# MCU_board_3.net
KiCad netlist of a schematic drawn in Altium Designer
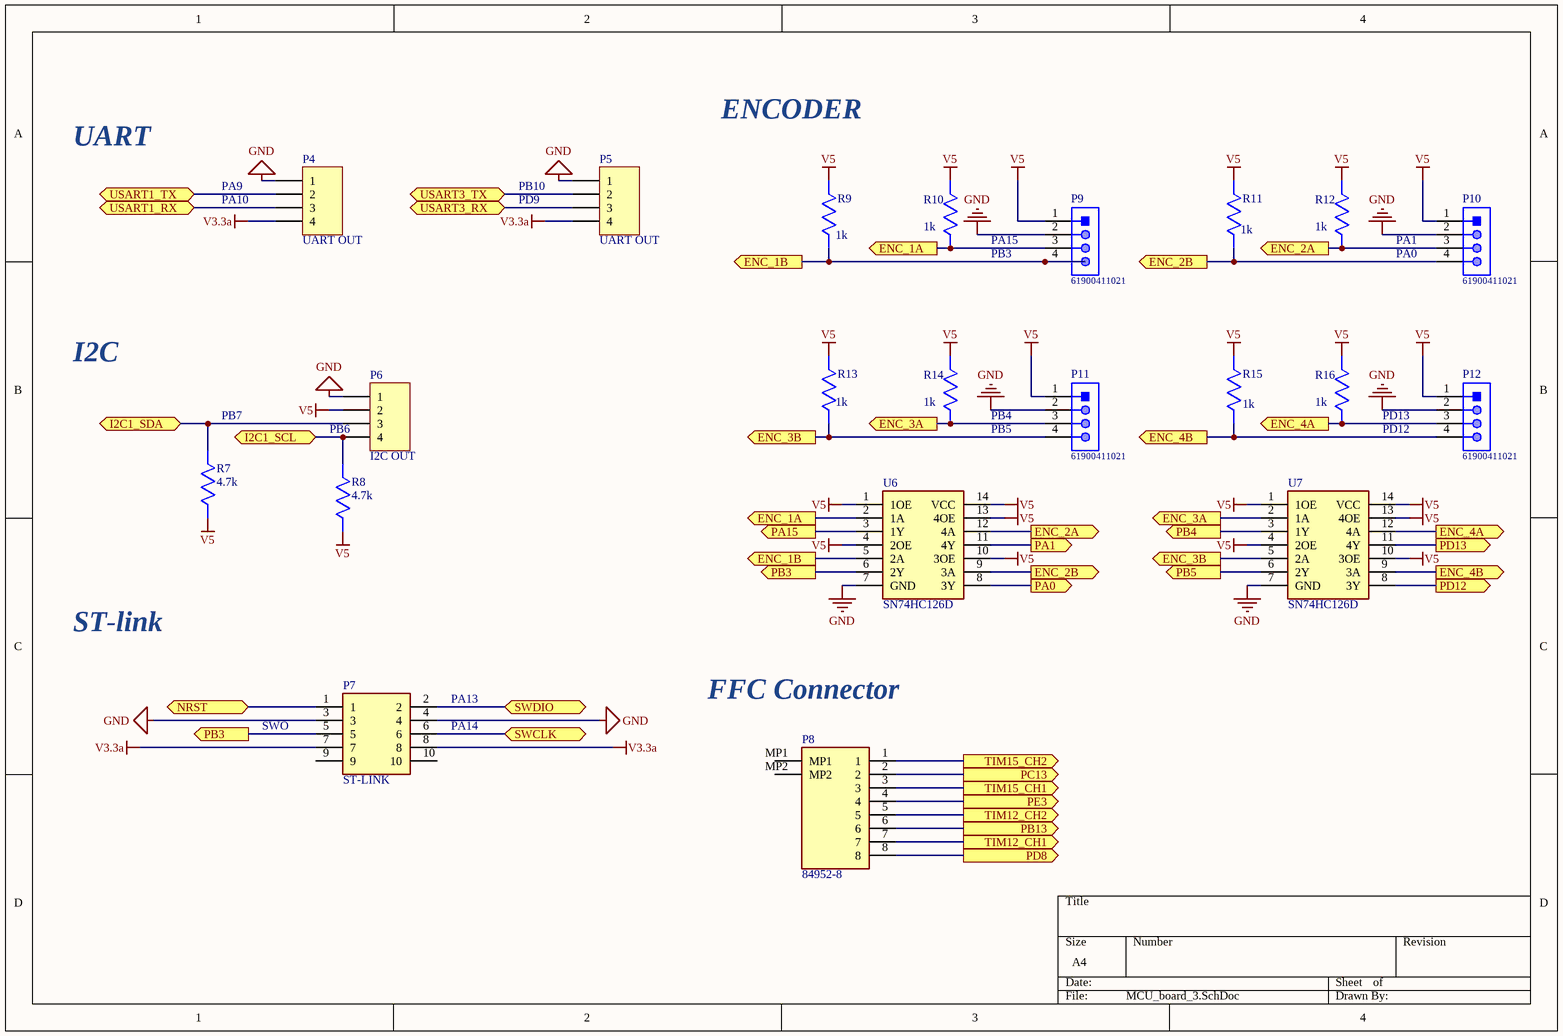
[diagram p0: MCU_board_3.SchDoc]

(export (version "E")
  (design (tool "Eeschema 10.0.6"))
  (components
    (comp (ref "P4")
      (value "UART OUT")
      (footprint "HDR1X4")
      (description "Header, 4-Pin")
      (fields (field (name "PUBLISHER") "Altium Limited"))
      (libsource (lib "Miscellaneous Connectors") (part "Header 4"))
    )
    (comp (ref "P5")
      (value "UART OUT")
      (footprint "HDR1X4")
      (description "Header, 4-Pin")
      (fields (field (name "PUBLISHER") "Altium Limited"))
      (libsource (lib "Miscellaneous Connectors") (part "Header 4"))
    )
    (comp (ref "P6")
      (value "I2C OUT")
      (footprint "HDR1X4")
      (description "Header, 4-Pin")
      (fields (field (name "PUBLISHER") "Altium Limited"))
      (libsource (lib "Miscellaneous Connectors") (part "Header 4"))
    )
    (comp (ref "P7")
      (value "ST-LINK")
      (footprint "SamacSys:SHDR10W66P254_2X5_2035X880X920P")
      (description "Connector")
      (fields (field (name "MANUFACTURER_PART_NUMBER") "1-1634688-0"))
      (libsource (lib "*") (part "1-1634688-0"))
    )
    (comp (ref "P8")
      (value "84952-8")
      (footprint "SamacSys:849528")
      (description "Connector")
      (fields (field (name "MOUSER PART NUMBER") "571-84952-8"))
      (libsource (lib "*") (part "84952-8"))
    )
    (comp (ref "P9")
      (value "61900411021")
      (footprint "61900411021")
      (description "Male Bottom Locking Header WR-WTB, THT, Right Angled, pitch 2.54 mm, 1 x 4 position")
      (fields (field (name "MANUFACTURER") "Wurth Elektronik") (field (name "PUBLISHER") "WurthElektronik"))
      (libsource (lib "Altium Content Vault") (part "WE-CN-1P-M-R4"))
    )
    (comp (ref "P10")
      (value "61900411021")
      (footprint "61900411021")
      (description "Male Bottom Locking Header WR-WTB, THT, Right Angled, pitch 2.54 mm, 1 x 4 position")
      (fields (field (name "MANUFACTURER") "Wurth Elektronik") (field (name "PUBLISHER") "WurthElektronik"))
      (libsource (lib "Altium Content Vault") (part "WE-CN-1P-M-R4"))
    )
    (comp (ref "P11")
      (value "61900411021")
      (footprint "61900411021")
      (description "Male Bottom Locking Header WR-WTB, THT, Right Angled, pitch 2.54 mm, 1 x 4 position")
      (fields (field (name "MANUFACTURER") "Wurth Elektronik") (field (name "PUBLISHER") "WurthElektronik"))
      (libsource (lib "Altium Content Vault") (part "WE-CN-1P-M-R4"))
    )
    (comp (ref "P12")
      (value "61900411021")
      (footprint "61900411021")
      (description "Male Bottom Locking Header WR-WTB, THT, Right Angled, pitch 2.54 mm, 1 x 4 position")
      (fields (field (name "MANUFACTURER") "Wurth Elektronik") (field (name "PUBLISHER") "WurthElektronik"))
      (libsource (lib "Altium Content Vault") (part "WE-CN-1P-M-R4"))
    )
    (comp (ref "R7")
      (value "4.7k")
      (footprint "SamacSys:RESC1608X55N")
      (description "Resistor")
      (fields (field (name "MANUFACTURER_PART_NUMBER") "CMP0603-FX-1003ELF"))
      (libsource (lib "SamacSys") (part "CMP0603-FX-1003ELF"))
    )
    (comp (ref "R8")
      (value "4.7k")
      (footprint "SamacSys:RESC1608X55N")
      (description "Resistor")
      (fields (field (name "MANUFACTURER_PART_NUMBER") "CMP0603-FX-1003ELF"))
      (libsource (lib "SamacSys") (part "CMP0603-FX-1003ELF"))
    )
    (comp (ref "R9")
      (value "1k")
      (footprint "SamacSys:RESC1608X55N")
      (description "Resistor")
      (fields (field (name "MANUFACTURER_PART_NUMBER") "CMP0603-FX-1003ELF"))
      (libsource (lib "SamacSys") (part "CMP0603-FX-1003ELF"))
    )
    (comp (ref "R10")
      (value "1k")
      (footprint "SamacSys:RESC1608X55N")
      (description "Resistor")
      (fields (field (name "MANUFACTURER_PART_NUMBER") "CMP0603-FX-1003ELF"))
      (libsource (lib "SamacSys") (part "CMP0603-FX-1003ELF"))
    )
    (comp (ref "R11")
      (value "1k")
      (footprint "SamacSys:RESC1608X55N")
      (description "Resistor")
      (fields (field (name "MANUFACTURER_PART_NUMBER") "CMP0603-FX-1003ELF"))
      (libsource (lib "SamacSys") (part "CMP0603-FX-1003ELF"))
    )
    (comp (ref "R12")
      (value "1k")
      (footprint "SamacSys:RESC1608X55N")
      (description "Resistor")
      (fields (field (name "MANUFACTURER_PART_NUMBER") "CMP0603-FX-1003ELF"))
      (libsource (lib "SamacSys") (part "CMP0603-FX-1003ELF"))
    )
    (comp (ref "R13")
      (value "1k")
      (footprint "SamacSys:RESC1608X55N")
      (description "Resistor")
      (fields (field (name "MANUFACTURER_PART_NUMBER") "CMP0603-FX-1003ELF"))
      (libsource (lib "SamacSys") (part "CMP0603-FX-1003ELF"))
    )
    (comp (ref "R14")
      (value "1k")
      (footprint "SamacSys:RESC1608X55N")
      (description "Resistor")
      (fields (field (name "MANUFACTURER_PART_NUMBER") "CMP0603-FX-1003ELF"))
      (libsource (lib "SamacSys") (part "CMP0603-FX-1003ELF"))
    )
    (comp (ref "R15")
      (value "1k")
      (footprint "SamacSys:RESC1608X55N")
      (description "Resistor")
      (fields (field (name "MANUFACTURER_PART_NUMBER") "CMP0603-FX-1003ELF"))
      (libsource (lib "SamacSys") (part "CMP0603-FX-1003ELF"))
    )
    (comp (ref "R16")
      (value "1k")
      (footprint "SamacSys:RESC1608X55N")
      (description "Resistor")
      (fields (field (name "MANUFACTURER_PART_NUMBER") "CMP0603-FX-1003ELF"))
      (libsource (lib "SamacSys") (part "CMP0603-FX-1003ELF"))
    )
    (comp (ref "U6")
      (value "SN74HC126D")
      (footprint "SamacSys:SOIC127P600X175-14N")
      (description "Integrated Circuit")
      (fields (field (name "MOUSER PART NUMBER") "595-SN74HC126D"))
      (libsource (lib "*") (part "SN74HC126D"))
    )
    (comp (ref "U7")
      (value "SN74HC126D")
      (footprint "SamacSys:SOIC127P600X175-14N")
      (description "Integrated Circuit")
      (fields (field (name "MOUSER PART NUMBER") "595-SN74HC126D"))
      (libsource (lib "*") (part "SN74HC126D"))
    )
  )
  (nets
    (net (code "1") (name "/ENC_1A") (class "Default")
      (node (ref "P9") (pin "3") (pinfunction "3_3") (pintype "passive"))
      (node (ref "R10") (pin "1") (pinfunction "1_1") (pintype "passive"))
      (node (ref "U6") (pin "2") (pinfunction "1A_2") (pintype "passive"))
    )
    (net (code "2") (name "/ENC_1B") (class "Default")
      (node (ref "P9") (pin "4") (pinfunction "4_4") (pintype "passive"))
      (node (ref "R9") (pin "1") (pinfunction "1_1") (pintype "passive"))
      (node (ref "U6") (pin "5") (pinfunction "2A_5") (pintype "passive"))
    )
    (net (code "3") (name "/ENC_2A") (class "Default")
      (node (ref "P10") (pin "3") (pinfunction "3_3") (pintype "passive"))
      (node (ref "R12") (pin "1") (pinfunction "1_1") (pintype "passive"))
      (node (ref "U6") (pin "12") (pinfunction "4A_12") (pintype "passive"))
    )
    (net (code "4") (name "/ENC_2B") (class "Default")
      (node (ref "P10") (pin "4") (pinfunction "4_4") (pintype "passive"))
      (node (ref "R11") (pin "1") (pinfunction "1_1") (pintype "passive"))
      (node (ref "U6") (pin "9") (pinfunction "3A_9") (pintype "passive"))
    )
    (net (code "5") (name "/ENC_3A") (class "Default")
      (node (ref "P11") (pin "3") (pinfunction "3_3") (pintype "passive"))
      (node (ref "R14") (pin "1") (pinfunction "1_1") (pintype "passive"))
      (node (ref "U7") (pin "2") (pinfunction "1A_2") (pintype "passive"))
    )
    (net (code "6") (name "/ENC_3B") (class "Default")
      (node (ref "P11") (pin "4") (pinfunction "4_4") (pintype "passive"))
      (node (ref "R13") (pin "1") (pinfunction "1_1") (pintype "passive"))
      (node (ref "U7") (pin "5") (pinfunction "2A_5") (pintype "passive"))
    )
    (net (code "7") (name "/ENC_4A") (class "Default")
      (node (ref "P12") (pin "3") (pinfunction "3_3") (pintype "passive"))
      (node (ref "R16") (pin "1") (pinfunction "1_1") (pintype "passive"))
      (node (ref "U7") (pin "12") (pinfunction "4A_12") (pintype "passive"))
    )
    (net (code "8") (name "/ENC_4B") (class "Default")
      (node (ref "P12") (pin "4") (pinfunction "4_4") (pintype "passive"))
      (node (ref "R15") (pin "1") (pinfunction "1_1") (pintype "passive"))
      (node (ref "U7") (pin "9") (pinfunction "3A_9") (pintype "passive"))
    )
    (net (code "9") (name "/I2C1_SCL") (class "Default")
      (node (ref "P6") (pin "4") (pinfunction "4_4") (pintype "passive"))
      (node (ref "R8") (pin "2") (pinfunction "2_2") (pintype "passive"))
    )
    (net (code "10") (name "/I2C1_SDA") (class "Default")
      (node (ref "P6") (pin "3") (pinfunction "3_3") (pintype "passive"))
      (node (ref "R7") (pin "2") (pinfunction "2_2") (pintype "passive"))
    )
    (net (code "11") (name "/NRST") (class "Default")
      (node (ref "P7") (pin "1") (pinfunction "1_1") (pintype "passive"))
    )
    (net (code "12") (name "/PA0") (class "Default")
      (node (ref "U6") (pin "8") (pinfunction "3Y_8") (pintype "passive"))
    )
    (net (code "13") (name "/PA1") (class "Default")
      (node (ref "U6") (pin "11") (pinfunction "4Y_11") (pintype "passive"))
    )
    (net (code "14") (name "/PA15") (class "Default")
      (node (ref "U6") (pin "3") (pinfunction "1Y_3") (pintype "passive"))
    )
    (net (code "15") (name "/PB3") (class "Default")
      (node (ref "P7") (pin "5") (pinfunction "5_5") (pintype "passive"))
      (node (ref "U6") (pin "6") (pinfunction "2Y_6") (pintype "passive"))
    )
    (net (code "16") (name "/PB4") (class "Default")
      (node (ref "U7") (pin "3") (pinfunction "1Y_3") (pintype "passive"))
    )
    (net (code "17") (name "/PB5") (class "Default")
      (node (ref "U7") (pin "6") (pinfunction "2Y_6") (pintype "passive"))
    )
    (net (code "18") (name "/PB13") (class "Default")
      (node (ref "P8") (pin "6") (pinfunction "6_6") (pintype "passive"))
    )
    (net (code "19") (name "/PC13") (class "Default")
      (node (ref "P8") (pin "2") (pinfunction "2_2") (pintype "passive"))
    )
    (net (code "20") (name "/PD8") (class "Default")
      (node (ref "P8") (pin "8") (pinfunction "8_8") (pintype "passive"))
    )
    (net (code "21") (name "/PD12") (class "Default")
      (node (ref "U7") (pin "8") (pinfunction "3Y_8") (pintype "passive"))
    )
    (net (code "22") (name "/PD13") (class "Default")
      (node (ref "U7") (pin "11") (pinfunction "4Y_11") (pintype "passive"))
    )
    (net (code "23") (name "/PE3") (class "Default")
      (node (ref "P8") (pin "4") (pinfunction "4_4") (pintype "passive"))
    )
    (net (code "24") (name "/SWCLK") (class "Default")
      (node (ref "P7") (pin "6") (pinfunction "6_6") (pintype "passive"))
    )
    (net (code "25") (name "/SWDIO") (class "Default")
      (node (ref "P7") (pin "2") (pinfunction "2_2") (pintype "passive"))
    )
    (net (code "26") (name "/TIM12_CH1") (class "Default")
      (node (ref "P8") (pin "7") (pinfunction "7_7") (pintype "passive"))
    )
    (net (code "27") (name "/TIM12_CH2") (class "Default")
      (node (ref "P8") (pin "5") (pinfunction "5_5") (pintype "passive"))
    )
    (net (code "28") (name "/TIM15_CH1") (class "Default")
      (node (ref "P8") (pin "3") (pinfunction "3_3") (pintype "passive"))
    )
    (net (code "29") (name "/TIM15_CH2") (class "Default")
      (node (ref "P8") (pin "1") (pinfunction "1_1") (pintype "passive"))
    )
    (net (code "30") (name "/USART1_RX") (class "Default")
      (node (ref "P4") (pin "3") (pinfunction "3_3") (pintype "passive"))
    )
    (net (code "31") (name "/USART1_TX") (class "Default")
      (node (ref "P4") (pin "2") (pinfunction "2_2") (pintype "passive"))
    )
    (net (code "32") (name "/USART3_RX") (class "Default")
      (node (ref "P5") (pin "3") (pinfunction "3_3") (pintype "passive"))
    )
    (net (code "33") (name "/USART3_TX") (class "Default")
      (node (ref "P5") (pin "2") (pinfunction "2_2") (pintype "passive"))
    )
    (net (code "34") (name "GND") (class "Default")
      (node (ref "P10") (pin "2") (pinfunction "2_2") (pintype "passive"))
      (node (ref "P11") (pin "2") (pinfunction "2_2") (pintype "passive"))
      (node (ref "P12") (pin "2") (pinfunction "2_2") (pintype "passive"))
      (node (ref "P4") (pin "1") (pinfunction "1_1") (pintype "passive"))
      (node (ref "P5") (pin "1") (pinfunction "1_1") (pintype "passive"))
      (node (ref "P6") (pin "1") (pinfunction "1_1") (pintype "passive"))
      (node (ref "P7") (pin "3") (pinfunction "3_3") (pintype "passive"))
      (node (ref "P7") (pin "4") (pinfunction "4_4") (pintype "passive"))
      (node (ref "P9") (pin "2") (pinfunction "2_2") (pintype "passive"))
      (node (ref "U6") (pin "7") (pinfunction "GND_7") (pintype "passive"))
      (node (ref "U7") (pin "7") (pinfunction "GND_7") (pintype "passive"))
    )
    (net (code "35") (name "V3.3a") (class "Default")
      (node (ref "P4") (pin "4") (pinfunction "4_4") (pintype "passive"))
      (node (ref "P5") (pin "4") (pinfunction "4_4") (pintype "passive"))
      (node (ref "P7") (pin "7") (pinfunction "7_7") (pintype "passive"))
      (node (ref "P7") (pin "8") (pinfunction "8_8") (pintype "passive"))
    )
    (net (code "36") (name "V5") (class "Default")
      (node (ref "P10") (pin "1") (pinfunction "1_1") (pintype "passive"))
      (node (ref "P11") (pin "1") (pinfunction "1_1") (pintype "passive"))
      (node (ref "P12") (pin "1") (pinfunction "1_1") (pintype "passive"))
      (node (ref "P6") (pin "2") (pinfunction "2_2") (pintype "passive"))
      (node (ref "P9") (pin "1") (pinfunction "1_1") (pintype "passive"))
      (node (ref "R10") (pin "2") (pinfunction "2_2") (pintype "passive"))
      (node (ref "R11") (pin "2") (pinfunction "2_2") (pintype "passive"))
      (node (ref "R12") (pin "2") (pinfunction "2_2") (pintype "passive"))
      (node (ref "R13") (pin "2") (pinfunction "2_2") (pintype "passive"))
      (node (ref "R14") (pin "2") (pinfunction "2_2") (pintype "passive"))
      (node (ref "R15") (pin "2") (pinfunction "2_2") (pintype "passive"))
      (node (ref "R16") (pin "2") (pinfunction "2_2") (pintype "passive"))
      (node (ref "R7") (pin "1") (pinfunction "1_1") (pintype "passive"))
      (node (ref "R8") (pin "1") (pinfunction "1_1") (pintype "passive"))
      (node (ref "R9") (pin "2") (pinfunction "2_2") (pintype "passive"))
      (node (ref "U6") (pin "1") (pinfunction "1OE_1") (pintype "passive"))
      (node (ref "U6") (pin "10") (pinfunction "3OE_10") (pintype "passive"))
      (node (ref "U6") (pin "13") (pinfunction "4OE_13") (pintype "passive"))
      (node (ref "U6") (pin "14") (pinfunction "VCC_14") (pintype "passive"))
      (node (ref "U6") (pin "4") (pinfunction "2OE_4") (pintype "passive"))
      (node (ref "U7") (pin "1") (pinfunction "1OE_1") (pintype "passive"))
      (node (ref "U7") (pin "10") (pinfunction "3OE_10") (pintype "passive"))
      (node (ref "U7") (pin "13") (pinfunction "4OE_13") (pintype "passive"))
      (node (ref "U7") (pin "14") (pinfunction "VCC_14") (pintype "passive"))
      (node (ref "U7") (pin "4") (pinfunction "2OE_4") (pintype "passive"))
    )
    (net (code "37") (name "unconnected-(P7-Pad9)") (class "Default")
      (node (ref "P7") (pin "9") (pinfunction "9_9") (pintype "passive"))
    )
    (net (code "38") (name "unconnected-(P7-Pad10)") (class "Default")
      (node (ref "P7") (pin "10") (pinfunction "10_10") (pintype "passive"))
    )
    (net (code "39") (name "unconnected-(P8-PadMP1)") (class "Default")
      (node (ref "P8") (pin "MP1") (pinfunction "MP1_MP1") (pintype "passive"))
    )
    (net (code "40") (name "unconnected-(P8-PadMP2)") (class "Default")
      (node (ref "P8") (pin "MP2") (pinfunction "MP2_MP2") (pintype "passive"))
    )
  )
)
